# oscilloscope.net
KiCad netlist of a schematic drawn in EAGLE
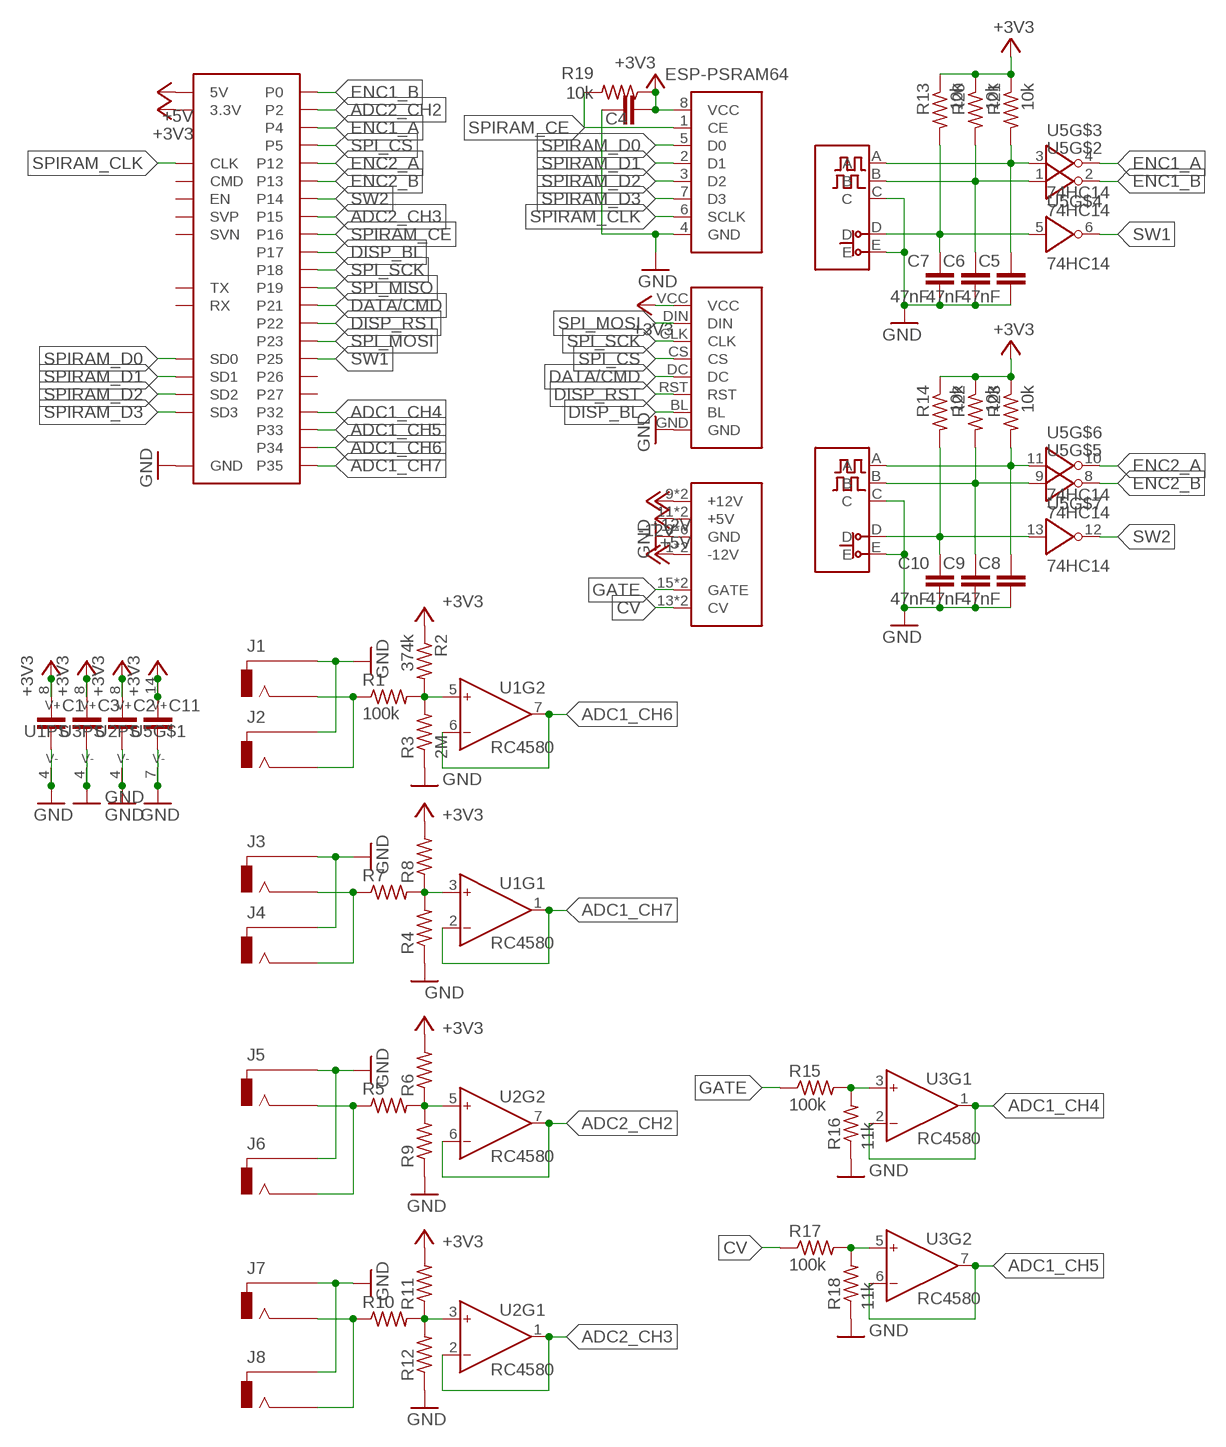
[diagram p0: schematic, sheet 1]

(export (version "E")
  (design (tool "Eeschema 10.0.6"))
  (components
    (comp (ref "C1")
      (value "C-EUC0805")
      (footprint "eagle-import:C0805")
      (libsource (lib "eagle-import") (part "C-EUC0805"))
    )
    (comp (ref "C2")
      (value "C-EUC0805")
      (footprint "eagle-import:C0805")
      (libsource (lib "eagle-import") (part "C-EUC0805"))
    )
    (comp (ref "C3")
      (value "C-EUC0805")
      (footprint "eagle-import:C0805")
      (libsource (lib "eagle-import") (part "C-EUC0805"))
    )
    (comp (ref "C4")
      (value "C-EUC0805")
      (footprint "eagle-import:C0805")
      (libsource (lib "eagle-import") (part "C-EUC0805"))
    )
    (comp (ref "C5")
      (value "47nF")
      (footprint "eagle-import:C0805")
      (libsource (lib "eagle-import") (part "C-EUC0805"))
    )
    (comp (ref "C6")
      (value "47nF")
      (footprint "eagle-import:C0805")
      (libsource (lib "eagle-import") (part "C-EUC0805"))
    )
    (comp (ref "C7")
      (value "47nF")
      (footprint "eagle-import:C0805")
      (libsource (lib "eagle-import") (part "C-EUC0805"))
    )
    (comp (ref "C8")
      (value "47nF")
      (footprint "eagle-import:C0805")
      (libsource (lib "eagle-import") (part "C-EUC0805"))
    )
    (comp (ref "C9")
      (value "47nF")
      (footprint "eagle-import:C0805")
      (libsource (lib "eagle-import") (part "C-EUC0805"))
    )
    (comp (ref "C10")
      (value "47nF")
      (footprint "eagle-import:C0805")
      (libsource (lib "eagle-import") (part "C-EUC0805"))
    )
    (comp (ref "C11")
      (value "C-EUC0805")
      (footprint "eagle-import:C0805")
      (libsource (lib "eagle-import") (part "C-EUC0805"))
    )
    (comp (ref "DS1")
      (value "ST27789_DISPLAY")
      (footprint "eagle-import:ST7789_DISPLAY")
      (libsource (lib "eagle-import") (part "ST27789_DISPLAY"))
    )
    (comp (ref "J1")
      (value "35PM1")
      (footprint "eagle-import:35PM1")
      (libsource (lib "eagle-import") (part "35PM1"))
    )
    (comp (ref "J2")
      (value "35PM1")
      (footprint "eagle-import:35PM1")
      (libsource (lib "eagle-import") (part "35PM1"))
    )
    (comp (ref "J3")
      (value "35PM1")
      (footprint "eagle-import:35PM1")
      (libsource (lib "eagle-import") (part "35PM1"))
    )
    (comp (ref "J4")
      (value "35PM1")
      (footprint "eagle-import:35PM1")
      (libsource (lib "eagle-import") (part "35PM1"))
    )
    (comp (ref "J5")
      (value "35PM1")
      (footprint "eagle-import:35PM1")
      (libsource (lib "eagle-import") (part "35PM1"))
    )
    (comp (ref "J6")
      (value "35PM1")
      (footprint "eagle-import:35PM1")
      (libsource (lib "eagle-import") (part "35PM1"))
    )
    (comp (ref "J7")
      (value "35PM1")
      (footprint "eagle-import:35PM1")
      (libsource (lib "eagle-import") (part "35PM1"))
    )
    (comp (ref "J8")
      (value "35PM1")
      (footprint "eagle-import:35PM1")
      (libsource (lib "eagle-import") (part "35PM1"))
    )
    (comp (ref "M1")
      (value "ESP32")
      (footprint "eagle-import:ESP32")
      (libsource (lib "eagle-import") (part "ESP32"))
    )
    (comp (ref "R1")
      (value "100k")
      (footprint "eagle-import:R0805")
      (libsource (lib "eagle-import") (part "R-US_R0805"))
    )
    (comp (ref "R2")
      (value "374k")
      (footprint "eagle-import:R0805")
      (libsource (lib "eagle-import") (part "R-US_R0805"))
    )
    (comp (ref "R3")
      (value "2M")
      (footprint "eagle-import:R0805")
      (libsource (lib "eagle-import") (part "R-US_R0805"))
    )
    (comp (ref "R4")
      (value "R-US_R0805")
      (footprint "eagle-import:R0805")
      (libsource (lib "eagle-import") (part "R-US_R0805"))
    )
    (comp (ref "R5")
      (value "R-US_R0805")
      (footprint "eagle-import:R0805")
      (libsource (lib "eagle-import") (part "R-US_R0805"))
    )
    (comp (ref "R6")
      (value "R-US_R0805")
      (footprint "eagle-import:R0805")
      (libsource (lib "eagle-import") (part "R-US_R0805"))
    )
    (comp (ref "R7")
      (value "R-US_R0805")
      (footprint "eagle-import:R0805")
      (libsource (lib "eagle-import") (part "R-US_R0805"))
    )
    (comp (ref "R8")
      (value "R-US_R0805")
      (footprint "eagle-import:R0805")
      (libsource (lib "eagle-import") (part "R-US_R0805"))
    )
    (comp (ref "R9")
      (value "R-US_R0805")
      (footprint "eagle-import:R0805")
      (libsource (lib "eagle-import") (part "R-US_R0805"))
    )
    (comp (ref "R10")
      (value "R-US_R0805")
      (footprint "eagle-import:R0805")
      (libsource (lib "eagle-import") (part "R-US_R0805"))
    )
    (comp (ref "R11")
      (value "R-US_R0805")
      (footprint "eagle-import:R0805")
      (libsource (lib "eagle-import") (part "R-US_R0805"))
    )
    (comp (ref "R12")
      (value "R-US_R0805")
      (footprint "eagle-import:R0805")
      (libsource (lib "eagle-import") (part "R-US_R0805"))
    )
    (comp (ref "R13")
      (value "10k")
      (footprint "eagle-import:R0805")
      (libsource (lib "eagle-import") (part "R-US_R0805"))
    )
    (comp (ref "R14")
      (value "10k")
      (footprint "eagle-import:R0805")
      (libsource (lib "eagle-import") (part "R-US_R0805"))
    )
    (comp (ref "R15")
      (value "100k")
      (footprint "eagle-import:R0805")
      (libsource (lib "eagle-import") (part "R-US_R0805"))
    )
    (comp (ref "R16")
      (value "11k")
      (footprint "eagle-import:R0805")
      (libsource (lib "eagle-import") (part "R-US_R0805"))
    )
    (comp (ref "R17")
      (value "100k")
      (footprint "eagle-import:R0805")
      (libsource (lib "eagle-import") (part "R-US_R0805"))
    )
    (comp (ref "R18")
      (value "11k")
      (footprint "eagle-import:R0805")
      (libsource (lib "eagle-import") (part "R-US_R0805"))
    )
    (comp (ref "R19")
      (value "10k")
      (footprint "eagle-import:R0805")
      (libsource (lib "eagle-import") (part "R-US_R0805"))
    )
    (comp (ref "R20")
      (value "10k")
      (footprint "eagle-import:R0805")
      (libsource (lib "eagle-import") (part "R-US_R0805"))
    )
    (comp (ref "R21")
      (value "10k")
      (footprint "eagle-import:R0805")
      (libsource (lib "eagle-import") (part "R-US_R0805"))
    )
    (comp (ref "R22")
      (value "10k")
      (footprint "eagle-import:R0805")
      (libsource (lib "eagle-import") (part "R-US_R0805"))
    )
    (comp (ref "R23")
      (value "10k")
      (footprint "eagle-import:R0805")
      (libsource (lib "eagle-import") (part "R-US_R0805"))
    )
    (comp (ref "SW1")
      (value "EN12-HS")
      (footprint "eagle-import:EN12-HS")
      (libsource (lib "eagle-import") (part "EN12-HS"))
    )
    (comp (ref "SW2")
      (value "EN12-HS")
      (footprint "eagle-import:EN12-HS")
      (libsource (lib "eagle-import") (part "EN12-HS"))
    )
    (comp (ref "U$1")
      (value "EURORACK")
      (footprint "eagle-import:302-S161")
      (libsource (lib "eagle-import") (part "EURORACK"))
    )
    (comp (ref "U1")
      (value "RC4580")
      (footprint "eagle-import:SOIC-8")
      (libsource (lib "eagle-import") (part "RC4580"))
    )
    (comp (ref "U2")
      (value "RC4580")
      (footprint "eagle-import:SOIC-8")
      (libsource (lib "eagle-import") (part "RC4580"))
    )
    (comp (ref "U3")
      (value "RC4580")
      (footprint "eagle-import:SOIC-8")
      (libsource (lib "eagle-import") (part "RC4580"))
    )
    (comp (ref "U4")
      (value "ESP-PSRAM64")
      (footprint "eagle-import:SOIC-8")
      (libsource (lib "eagle-import") (part "ESP-PSRAM64"))
    )
    (comp (ref "U5")
      (value "74HC14")
      (footprint "eagle-import:SOIC127P600X175-14N")
      (libsource (lib "eagle-import") (part "74HC14"))
    )
  )
  (nets
    (net (code "1") (name "+3V3") (class "Default")
      (node (ref "C1") (pin "1") (pinfunction "1_1") (pintype "passive"))
      (node (ref "C11") (pin "1") (pinfunction "1_1") (pintype "passive"))
      (node (ref "C2") (pin "1") (pinfunction "1_1") (pintype "passive"))
      (node (ref "C3") (pin "1") (pinfunction "1_1") (pintype "passive"))
      (node (ref "C4") (pin "2") (pinfunction "2_2") (pintype "passive"))
      (node (ref "DS1") (pin "VCC") (pinfunction "VCC_VCC") (pintype "bidirectional"))
      (node (ref "M1") (pin "X0") (pinfunction "3.3V_X0") (pintype "bidirectional"))
      (node (ref "R11") (pin "2") (pinfunction "2_2") (pintype "passive"))
      (node (ref "R13") (pin "1") (pinfunction "1_1") (pintype "passive"))
      (node (ref "R14") (pin "1") (pinfunction "1_1") (pintype "passive"))
      (node (ref "R19") (pin "1") (pinfunction "1_1") (pintype "passive"))
      (node (ref "R2") (pin "1") (pinfunction "1_1") (pintype "passive"))
      (node (ref "R20") (pin "1") (pinfunction "1_1") (pintype "passive"))
      (node (ref "R21") (pin "1") (pinfunction "1_1") (pintype "passive"))
      (node (ref "R22") (pin "1") (pinfunction "1_1") (pintype "passive"))
      (node (ref "R23") (pin "1") (pinfunction "1_1") (pintype "passive"))
      (node (ref "R6") (pin "2") (pinfunction "2_2") (pintype "passive"))
      (node (ref "R8") (pin "2") (pinfunction "2_2") (pintype "passive"))
      (node (ref "U1") (pin "8") (pinfunction "V+_8") (pintype "power_in"))
      (node (ref "U2") (pin "8") (pinfunction "V+_8") (pintype "power_in"))
      (node (ref "U3") (pin "8") (pinfunction "V+_8") (pintype "power_in"))
      (node (ref "U4") (pin "8") (pinfunction "VCC_8") (pintype "bidirectional"))
      (node (ref "U5") (pin "14") (pinfunction "V+_14") (pintype "power_in"))
    )
    (net (code "2") (name "+5V") (class "Default")
      (node (ref "M1") (pin "X18") (pinfunction "5V_X18") (pintype "bidirectional"))
      (node (ref "U$1") (pin "11") (pinfunction "+5V_11") (pintype "bidirectional"))
      (node (ref "U$1") (pin "12") (pinfunction "+5V_12") (pintype "bidirectional"))
    )
    (net (code "3") (name "+12V") (class "Default")
      (node (ref "U$1") (pin "10") (pinfunction "+12V_10") (pintype "bidirectional"))
      (node (ref "U$1") (pin "9") (pinfunction "+12V_9") (pintype "bidirectional"))
    )
    (net (code "4") (name "-12V") (class "Default")
      (node (ref "U$1") (pin "1") (pinfunction "-12V_1") (pintype "bidirectional"))
      (node (ref "U$1") (pin "2") (pinfunction "-12V_2") (pintype "bidirectional"))
    )
    (net (code "5") (name "ADC1_CH4") (class "Default")
      (node (ref "M1") (pin "X6") (pinfunction "P32_X6") (pintype "bidirectional"))
      (node (ref "U3") (pin "1") (pinfunction "OUT_1") (pintype "output"))
      (node (ref "U3") (pin "2") (pinfunction "IN-_2") (pintype "input"))
    )
    (net (code "6") (name "ADC1_CH5") (class "Default")
      (node (ref "M1") (pin "X7") (pinfunction "P33_X7") (pintype "bidirectional"))
      (node (ref "U3") (pin "6") (pinfunction "IN-_6") (pintype "input"))
      (node (ref "U3") (pin "7") (pinfunction "OUT_7") (pintype "output"))
    )
    (net (code "7") (name "ADC1_CH6") (class "Default")
      (node (ref "M1") (pin "X4") (pinfunction "P34_X4") (pintype "bidirectional"))
      (node (ref "U1") (pin "6") (pinfunction "IN-_6") (pintype "input"))
      (node (ref "U1") (pin "7") (pinfunction "OUT_7") (pintype "output"))
    )
    (net (code "8") (name "ADC1_CH7") (class "Default")
      (node (ref "M1") (pin "X5") (pinfunction "P35_X5") (pintype "bidirectional"))
      (node (ref "U1") (pin "1") (pinfunction "OUT_1") (pintype "output"))
      (node (ref "U1") (pin "2") (pinfunction "IN-_2") (pintype "input"))
    )
    (net (code "9") (name "ADC2_CH2") (class "Default")
      (node (ref "M1") (pin "X23") (pinfunction "P2_X23") (pintype "bidirectional"))
      (node (ref "U2") (pin "6") (pinfunction "IN-_6") (pintype "input"))
      (node (ref "U2") (pin "7") (pinfunction "OUT_7") (pintype "output"))
    )
    (net (code "10") (name "ADC2_CH3") (class "Default")
      (node (ref "M1") (pin "X22") (pinfunction "P15_X22") (pintype "bidirectional"))
      (node (ref "U2") (pin "1") (pinfunction "OUT_1") (pintype "output"))
      (node (ref "U2") (pin "2") (pinfunction "IN-_2") (pintype "input"))
    )
    (net (code "11") (name "CV") (class "Default")
      (node (ref "R17") (pin "1") (pinfunction "1_1") (pintype "passive"))
      (node (ref "U$1") (pin "13") (pinfunction "CV_13") (pintype "bidirectional"))
      (node (ref "U$1") (pin "14") (pinfunction "CV_14") (pintype "bidirectional"))
    )
    (net (code "12") (name "DATA{slash}CMD") (class "Default")
      (node (ref "DS1") (pin "DC") (pinfunction "DC_DC") (pintype "bidirectional"))
      (node (ref "M1") (pin "X32") (pinfunction "P21_X32") (pintype "bidirectional"))
    )
    (net (code "13") (name "DISP_BL") (class "Default")
      (node (ref "DS1") (pin "BL") (pinfunction "BL_BL") (pintype "bidirectional"))
      (node (ref "M1") (pin "X27") (pinfunction "P17_X27") (pintype "bidirectional"))
    )
    (net (code "14") (name "DISP_RST") (class "Default")
      (node (ref "DS1") (pin "RST") (pinfunction "RST_RST") (pintype "bidirectional"))
      (node (ref "M1") (pin "X35") (pinfunction "P22_X35") (pintype "bidirectional"))
    )
    (net (code "15") (name "ENC1_A") (class "Default")
      (node (ref "M1") (pin "X25") (pinfunction "P4_X25") (pintype "bidirectional"))
      (node (ref "U5") (pin "4") (pinfunction "O_4") (pintype "input"))
    )
    (net (code "16") (name "ENC1_B") (class "Default")
      (node (ref "M1") (pin "X24") (pinfunction "P0_X24") (pintype "bidirectional"))
      (node (ref "U5") (pin "2") (pinfunction "O_2") (pintype "input"))
    )
    (net (code "17") (name "ENC2_A") (class "Default")
      (node (ref "M1") (pin "X12") (pinfunction "P12_X12") (pintype "bidirectional"))
      (node (ref "U5") (pin "10") (pinfunction "O_10") (pintype "input"))
    )
    (net (code "18") (name "ENC2_B") (class "Default")
      (node (ref "M1") (pin "X14") (pinfunction "P13_X14") (pintype "bidirectional"))
      (node (ref "U5") (pin "8") (pinfunction "O_8") (pintype "input"))
    )
    (net (code "19") (name "GATE") (class "Default")
      (node (ref "R15") (pin "1") (pinfunction "1_1") (pintype "passive"))
      (node (ref "U$1") (pin "15") (pinfunction "GATE_15") (pintype "bidirectional"))
      (node (ref "U$1") (pin "16") (pinfunction "GATE_16") (pintype "bidirectional"))
    )
    (net (code "20") (name "GND") (class "Default")
      (node (ref "C1") (pin "2") (pinfunction "2_2") (pintype "passive"))
      (node (ref "C10") (pin "2") (pinfunction "2_2") (pintype "passive"))
      (node (ref "C11") (pin "2") (pinfunction "2_2") (pintype "passive"))
      (node (ref "C2") (pin "2") (pinfunction "2_2") (pintype "passive"))
      (node (ref "C3") (pin "2") (pinfunction "2_2") (pintype "passive"))
      (node (ref "C4") (pin "1") (pinfunction "1_1") (pintype "passive"))
      (node (ref "C5") (pin "2") (pinfunction "2_2") (pintype "passive"))
      (node (ref "C6") (pin "2") (pinfunction "2_2") (pintype "passive"))
      (node (ref "C7") (pin "2") (pinfunction "2_2") (pintype "passive"))
      (node (ref "C8") (pin "2") (pinfunction "2_2") (pintype "passive"))
      (node (ref "C9") (pin "2") (pinfunction "2_2") (pintype "passive"))
      (node (ref "DS1") (pin "GND") (pinfunction "GND_GND") (pintype "bidirectional"))
      (node (ref "J1") (pin "SLEEVE") (pinfunction "SLEEVE_SLEEVE") (pintype "passive"))
      (node (ref "J2") (pin "SLEEVE") (pinfunction "SLEEVE_SLEEVE") (pintype "passive"))
      (node (ref "J3") (pin "SLEEVE") (pinfunction "SLEEVE_SLEEVE") (pintype "passive"))
      (node (ref "J4") (pin "SLEEVE") (pinfunction "SLEEVE_SLEEVE") (pintype "passive"))
      (node (ref "J5") (pin "SLEEVE") (pinfunction "SLEEVE_SLEEVE") (pintype "passive"))
      (node (ref "J6") (pin "SLEEVE") (pinfunction "SLEEVE_SLEEVE") (pintype "passive"))
      (node (ref "J7") (pin "SLEEVE") (pinfunction "SLEEVE_SLEEVE") (pintype "passive"))
      (node (ref "J8") (pin "SLEEVE") (pinfunction "SLEEVE_SLEEVE") (pintype "passive"))
      (node (ref "M1") (pin "X13") (pinfunction "GND_X13") (pintype "bidirectional"))
      (node (ref "M1") (pin "X31") (pinfunction "GND_X31") (pintype "bidirectional"))
      (node (ref "M1") (pin "X37") (pinfunction "GND_X37") (pintype "bidirectional"))
      (node (ref "R12") (pin "1") (pinfunction "1_1") (pintype "passive"))
      (node (ref "R16") (pin "1") (pinfunction "1_1") (pintype "passive"))
      (node (ref "R18") (pin "1") (pinfunction "1_1") (pintype "passive"))
      (node (ref "R3") (pin "1") (pinfunction "1_1") (pintype "passive"))
      (node (ref "R4") (pin "1") (pinfunction "1_1") (pintype "passive"))
      (node (ref "R9") (pin "1") (pinfunction "1_1") (pintype "passive"))
      (node (ref "SW1") (pin "C") (pinfunction "C_C") (pintype "bidirectional"))
      (node (ref "SW1") (pin "E") (pinfunction "E_E") (pintype "bidirectional"))
      (node (ref "SW2") (pin "C") (pinfunction "C_C") (pintype "bidirectional"))
      (node (ref "SW2") (pin "E") (pinfunction "E_E") (pintype "bidirectional"))
      (node (ref "U$1") (pin "3") (pinfunction "GND_3") (pintype "bidirectional"))
      (node (ref "U$1") (pin "4") (pinfunction "GND_4") (pintype "bidirectional"))
      (node (ref "U$1") (pin "5") (pinfunction "GND_5") (pintype "bidirectional"))
      (node (ref "U$1") (pin "6") (pinfunction "GND_6") (pintype "bidirectional"))
      (node (ref "U$1") (pin "7") (pinfunction "GND_7") (pintype "bidirectional"))
      (node (ref "U$1") (pin "8") (pinfunction "GND_8") (pintype "bidirectional"))
      (node (ref "U1") (pin "4") (pinfunction "V-_4") (pintype "power_in"))
      (node (ref "U2") (pin "4") (pinfunction "V-_4") (pintype "power_in"))
      (node (ref "U3") (pin "4") (pinfunction "V-_4") (pintype "power_in"))
      (node (ref "U4") (pin "4") (pinfunction "GND_4") (pintype "bidirectional"))
      (node (ref "U5") (pin "7") (pinfunction "V-_7") (pintype "power_in"))
    )
    (net (code "21") (name "Net-(J1-PadTIP)") (class "Default")
      (node (ref "J1") (pin "TIP") (pinfunction "TIP_TIP") (pintype "passive"))
      (node (ref "J2") (pin "TIP") (pinfunction "TIP_TIP") (pintype "passive"))
      (node (ref "R1") (pin "1") (pinfunction "1_1") (pintype "passive"))
    )
    (net (code "22") (name "Net-(J3-PadTIP)") (class "Default")
      (node (ref "J3") (pin "TIP") (pinfunction "TIP_TIP") (pintype "passive"))
      (node (ref "J4") (pin "TIP") (pinfunction "TIP_TIP") (pintype "passive"))
      (node (ref "R7") (pin "1") (pinfunction "1_1") (pintype "passive"))
    )
    (net (code "23") (name "Net-(J5-PadTIP)") (class "Default")
      (node (ref "J5") (pin "TIP") (pinfunction "TIP_TIP") (pintype "passive"))
      (node (ref "J6") (pin "TIP") (pinfunction "TIP_TIP") (pintype "passive"))
      (node (ref "R5") (pin "1") (pinfunction "1_1") (pintype "passive"))
    )
    (net (code "24") (name "Net-(J7-PadTIP)") (class "Default")
      (node (ref "J7") (pin "TIP") (pinfunction "TIP_TIP") (pintype "passive"))
      (node (ref "J8") (pin "TIP") (pinfunction "TIP_TIP") (pintype "passive"))
      (node (ref "R10") (pin "1") (pinfunction "1_1") (pintype "passive"))
    )
    (net (code "25") (name "Net-(U1A-IN+)") (class "Default")
      (node (ref "R4") (pin "2") (pinfunction "2_2") (pintype "passive"))
      (node (ref "R7") (pin "2") (pinfunction "2_2") (pintype "passive"))
      (node (ref "R8") (pin "1") (pinfunction "1_1") (pintype "passive"))
      (node (ref "U1") (pin "3") (pinfunction "IN+_3") (pintype "input"))
    )
    (net (code "26") (name "Net-(U1B-IN+)") (class "Default")
      (node (ref "R1") (pin "2") (pinfunction "2_2") (pintype "passive"))
      (node (ref "R2") (pin "2") (pinfunction "2_2") (pintype "passive"))
      (node (ref "R3") (pin "2") (pinfunction "2_2") (pintype "passive"))
      (node (ref "U1") (pin "5") (pinfunction "IN+_5") (pintype "input"))
    )
    (net (code "27") (name "Net-(U2A-IN+)") (class "Default")
      (node (ref "R10") (pin "2") (pinfunction "2_2") (pintype "passive"))
      (node (ref "R11") (pin "1") (pinfunction "1_1") (pintype "passive"))
      (node (ref "R12") (pin "2") (pinfunction "2_2") (pintype "passive"))
      (node (ref "U2") (pin "3") (pinfunction "IN+_3") (pintype "input"))
    )
    (net (code "28") (name "Net-(U2B-IN+)") (class "Default")
      (node (ref "R5") (pin "2") (pinfunction "2_2") (pintype "passive"))
      (node (ref "R6") (pin "1") (pinfunction "1_1") (pintype "passive"))
      (node (ref "R9") (pin "2") (pinfunction "2_2") (pintype "passive"))
      (node (ref "U2") (pin "5") (pinfunction "IN+_5") (pintype "input"))
    )
    (net (code "29") (name "Net-(U3A-IN+)") (class "Default")
      (node (ref "R15") (pin "2") (pinfunction "2_2") (pintype "passive"))
      (node (ref "R16") (pin "2") (pinfunction "2_2") (pintype "passive"))
      (node (ref "U3") (pin "3") (pinfunction "IN+_3") (pintype "input"))
    )
    (net (code "30") (name "Net-(U3B-IN+)") (class "Default")
      (node (ref "R17") (pin "2") (pinfunction "2_2") (pintype "passive"))
      (node (ref "R18") (pin "2") (pinfunction "2_2") (pintype "passive"))
      (node (ref "U3") (pin "5") (pinfunction "IN+_5") (pintype "input"))
    )
    (net (code "31") (name "Net-(U5B-I)") (class "Default")
      (node (ref "C6") (pin "1") (pinfunction "1_1") (pintype "passive"))
      (node (ref "R20") (pin "2") (pinfunction "2_2") (pintype "passive"))
      (node (ref "SW1") (pin "B") (pinfunction "B_B") (pintype "bidirectional"))
      (node (ref "U5") (pin "1") (pinfunction "I_1") (pintype "input"))
    )
    (net (code "32") (name "Net-(U5C-I)") (class "Default")
      (node (ref "C5") (pin "1") (pinfunction "1_1") (pintype "passive"))
      (node (ref "R21") (pin "2") (pinfunction "2_2") (pintype "passive"))
      (node (ref "SW1") (pin "A") (pinfunction "A_A") (pintype "bidirectional"))
      (node (ref "U5") (pin "3") (pinfunction "I_3") (pintype "input"))
    )
    (net (code "33") (name "Net-(U5D-I)") (class "Default")
      (node (ref "C7") (pin "1") (pinfunction "1_1") (pintype "passive"))
      (node (ref "R13") (pin "2") (pinfunction "2_2") (pintype "passive"))
      (node (ref "SW1") (pin "D") (pinfunction "D_D") (pintype "bidirectional"))
      (node (ref "U5") (pin "5") (pinfunction "I_5") (pintype "input"))
    )
    (net (code "34") (name "Net-(U5E-I)") (class "Default")
      (node (ref "C9") (pin "1") (pinfunction "1_1") (pintype "passive"))
      (node (ref "R22") (pin "2") (pinfunction "2_2") (pintype "passive"))
      (node (ref "SW2") (pin "B") (pinfunction "B_B") (pintype "bidirectional"))
      (node (ref "U5") (pin "9") (pinfunction "I_9") (pintype "input"))
    )
    (net (code "35") (name "Net-(U5F-I)") (class "Default")
      (node (ref "C8") (pin "1") (pinfunction "1_1") (pintype "passive"))
      (node (ref "R23") (pin "2") (pinfunction "2_2") (pintype "passive"))
      (node (ref "SW2") (pin "A") (pinfunction "A_A") (pintype "bidirectional"))
      (node (ref "U5") (pin "11") (pinfunction "I_11") (pintype "input"))
    )
    (net (code "36") (name "Net-(U5G-I)") (class "Default")
      (node (ref "C10") (pin "1") (pinfunction "1_1") (pintype "passive"))
      (node (ref "R14") (pin "2") (pinfunction "2_2") (pintype "passive"))
      (node (ref "SW2") (pin "D") (pinfunction "D_D") (pintype "bidirectional"))
      (node (ref "U5") (pin "13") (pinfunction "I_13") (pintype "input"))
    )
    (net (code "37") (name "SPIRAM_CE") (class "Default")
      (node (ref "M1") (pin "X26") (pinfunction "P16_X26") (pintype "bidirectional"))
      (node (ref "R19") (pin "2") (pinfunction "2_2") (pintype "passive"))
      (node (ref "U4") (pin "1") (pinfunction "CE_1") (pintype "bidirectional"))
    )
    (net (code "38") (name "SPIRAM_CLK") (class "Default")
      (node (ref "M1") (pin "X19") (pinfunction "CLK_X19") (pintype "bidirectional"))
      (node (ref "U4") (pin "6") (pinfunction "SCLK_6") (pintype "bidirectional"))
    )
    (net (code "39") (name "SPIRAM_D0") (class "Default")
      (node (ref "M1") (pin "X20") (pinfunction "SD0_X20") (pintype "bidirectional"))
      (node (ref "U4") (pin "5") (pinfunction "D0_5") (pintype "bidirectional"))
    )
    (net (code "40") (name "SPIRAM_D1") (class "Default")
      (node (ref "M1") (pin "X21") (pinfunction "SD1_X21") (pintype "bidirectional"))
      (node (ref "U4") (pin "2") (pinfunction "D1_2") (pintype "bidirectional"))
    )
    (net (code "41") (name "SPIRAM_D2") (class "Default")
      (node (ref "M1") (pin "X15") (pinfunction "SD2_X15") (pintype "bidirectional"))
      (node (ref "U4") (pin "3") (pinfunction "D2_3") (pintype "bidirectional"))
    )
    (net (code "42") (name "SPIRAM_D3") (class "Default")
      (node (ref "M1") (pin "X16") (pinfunction "SD3_X16") (pintype "bidirectional"))
      (node (ref "U4") (pin "7") (pinfunction "D3_7") (pintype "bidirectional"))
    )
    (net (code "43") (name "SPI_CS") (class "Default")
      (node (ref "DS1") (pin "CS") (pinfunction "CS_CS") (pintype "bidirectional"))
      (node (ref "M1") (pin "X28") (pinfunction "P5_X28") (pintype "bidirectional"))
    )
    (net (code "44") (name "SPI_MISO") (class "Default")
      (node (ref "M1") (pin "X30") (pinfunction "P19_X30") (pintype "bidirectional"))
    )
    (net (code "45") (name "SPI_MOSI") (class "Default")
      (node (ref "DS1") (pin "DIN") (pinfunction "DIN_DIN") (pintype "bidirectional"))
      (node (ref "M1") (pin "X36") (pinfunction "P23_X36") (pintype "bidirectional"))
    )
    (net (code "46") (name "SPI_SCK") (class "Default")
      (node (ref "DS1") (pin "CLK") (pinfunction "CLK_CLK") (pintype "bidirectional"))
      (node (ref "M1") (pin "X29") (pinfunction "P18_X29") (pintype "bidirectional"))
    )
    (net (code "47") (name "SW1") (class "Default")
      (node (ref "M1") (pin "X8") (pinfunction "P25_X8") (pintype "bidirectional"))
      (node (ref "U5") (pin "6") (pinfunction "O_6") (pintype "input"))
    )
    (net (code "48") (name "SW2") (class "Default")
      (node (ref "M1") (pin "X11") (pinfunction "P14_X11") (pintype "bidirectional"))
      (node (ref "U5") (pin "12") (pinfunction "O_12") (pintype "input"))
    )
    (net (code "49") (name "unconnected-(M1-CMD-PadX17)") (class "Default")
      (node (ref "M1") (pin "X17") (pinfunction "CMD_X17") (pintype "bidirectional"))
    )
    (net (code "50") (name "unconnected-(M1-EN-PadX1)") (class "Default")
      (node (ref "M1") (pin "X1") (pinfunction "EN_X1") (pintype "bidirectional"))
    )
    (net (code "51") (name "unconnected-(M1-P26-PadX9)") (class "Default")
      (node (ref "M1") (pin "X9") (pinfunction "P26_X9") (pintype "bidirectional"))
    )
    (net (code "52") (name "unconnected-(M1-P27-PadX10)") (class "Default")
      (node (ref "M1") (pin "X10") (pinfunction "P27_X10") (pintype "bidirectional"))
    )
    (net (code "53") (name "unconnected-(M1-RX-PadX33)") (class "Default")
      (node (ref "M1") (pin "X33") (pinfunction "RX_X33") (pintype "bidirectional"))
    )
    (net (code "54") (name "unconnected-(M1-SVN-PadX3)") (class "Default")
      (node (ref "M1") (pin "X3") (pinfunction "SVN_X3") (pintype "bidirectional"))
    )
    (net (code "55") (name "unconnected-(M1-SVP-PadX2)") (class "Default")
      (node (ref "M1") (pin "X2") (pinfunction "SVP_X2") (pintype "bidirectional"))
    )
    (net (code "56") (name "unconnected-(M1-TX-PadX34)") (class "Default")
      (node (ref "M1") (pin "X34") (pinfunction "TX_X34") (pintype "bidirectional"))
    )
  )
)
